# MAXM86161.net
KiCad netlist of a schematic drawn in EAGLE
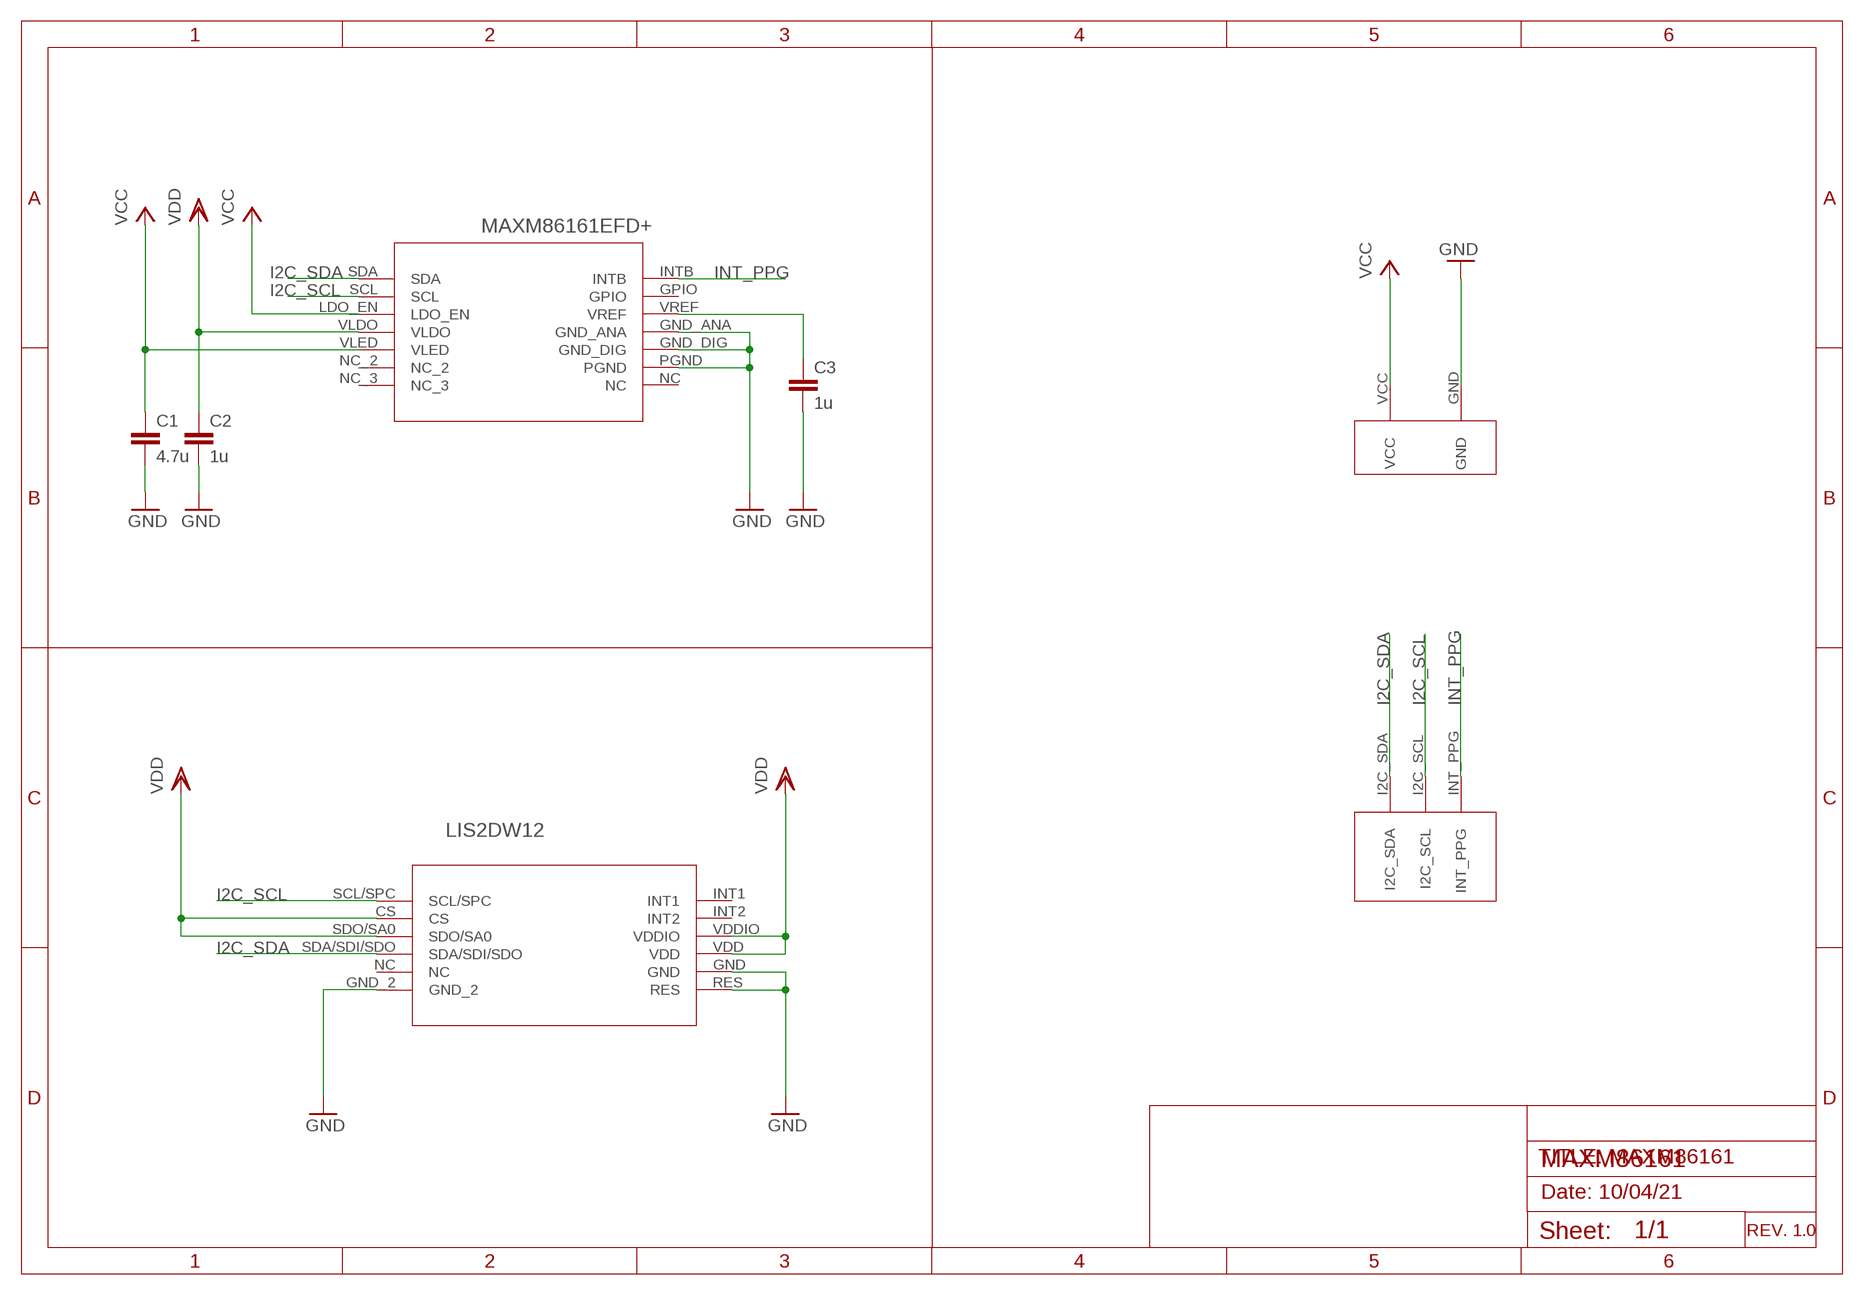
[diagram p0: schematic, sheet 1]

(export (version "E")
  (design (tool "Eeschema 10.0.6"))
  (components
    (comp (ref "C1")
      (value "4.7u")
      (footprint "eagle-import:C0603")
      (libsource (lib "eagle-import") (part "C0603"))
    )
    (comp (ref "C2")
      (value "1u")
      (footprint "eagle-import:C0402")
      (libsource (lib "eagle-import") (part "C0402"))
    )
    (comp (ref "C3")
      (value "1u")
      (footprint "eagle-import:C0402")
      (libsource (lib "eagle-import") (part "C0402"))
    )
    (comp (ref "U$1")
      (value "PAD_2")
      (footprint "eagle-import:PAD_2")
      (libsource (lib "eagle-import") (part "PAD_2"))
    )
    (comp (ref "U$2")
      (value "PAD_3")
      (footprint "eagle-import:PAD_3")
      (libsource (lib "eagle-import") (part "PAD_3"))
    )
    (comp (ref "U1")
      (value "MAXM86161EFD+")
      (footprint "eagle-import:21-100309A_MXM")
      (fields (field (name "COPYRIGHT") "Copyright (C) 2018 Accelerated Designs. All rights reserved"))
      (libsource (lib "eagle-import") (part "MAXM86161EFD+"))
    )
    (comp (ref "U2")
      (value "LIS2DW12")
      (footprint "eagle-import:LIS2DW12_LGA-12_2X2X0P7_STM")
      (libsource (lib "eagle-import") (part "LIS2DW12"))
    )
  )
  (nets
    (net (code "1") (name "/I2C_SCL") (class "Default")
      (node (ref "U$2") (pin "I2C_SCL") (pinfunction "I2C_SCL_I2C_SCL") (pintype "bidirectional"))
      (node (ref "U1") (pin "SCL") (pinfunction "SCL_SCL") (pintype "input"))
      (node (ref "U2") (pin "SCL/SPC") (pinfunction "SCL/SPC_SCL/SPC") (pintype "bidirectional"))
    )
    (net (code "2") (name "/I2C_SDA") (class "Default")
      (node (ref "U$2") (pin "I2C_SDA") (pinfunction "I2C_SDA_I2C_SDA") (pintype "bidirectional"))
      (node (ref "U1") (pin "SDA") (pinfunction "SDA_SDA") (pintype "bidirectional"))
      (node (ref "U2") (pin "SDA/SDI/SDO") (pinfunction "SDA/SDI/SDO_SDA/SDI/SDO") (pintype "bidirectional"))
    )
    (net (code "3") (name "/INT_PPG") (class "Default")
      (node (ref "U$2") (pin "INT_PPG") (pinfunction "INT_PPG_INT_PPG") (pintype "bidirectional"))
      (node (ref "U1") (pin "INTB") (pinfunction "INTB_INTB") (pintype "passive"))
    )
    (net (code "4") (name "GND") (class "Default")
      (node (ref "C1") (pin "P$2") (pinfunction "2_P$2") (pintype "passive"))
      (node (ref "C2") (pin "P$2") (pinfunction "2_P$2") (pintype "passive"))
      (node (ref "C3") (pin "P$2") (pinfunction "2_P$2") (pintype "passive"))
      (node (ref "U$1") (pin "GND") (pinfunction "GND_GND") (pintype "bidirectional"))
      (node (ref "U1") (pin "GND_ANA") (pinfunction "GND_ANA_GND_ANA") (pintype "passive"))
      (node (ref "U1") (pin "GND_DIG") (pinfunction "GND_DIG_GND_DIG") (pintype "passive"))
      (node (ref "U1") (pin "PGND") (pinfunction "PGND_PGND") (pintype "passive"))
      (node (ref "U2") (pin "GND") (pinfunction "GND_GND") (pintype "passive"))
      (node (ref "U2") (pin "GND_2") (pinfunction "GND_2_GND_2") (pintype "passive"))
      (node (ref "U2") (pin "RES") (pinfunction "RES_RES") (pintype "passive"))
    )
    (net (code "5") (name "Net-(C3-1)") (class "Default")
      (node (ref "C3") (pin "P$1") (pinfunction "1_P$1") (pintype "passive"))
      (node (ref "U1") (pin "VREF") (pinfunction "VREF_VREF") (pintype "passive"))
    )
    (net (code "6") (name "VCC") (class "Default")
      (node (ref "C1") (pin "P$1") (pinfunction "1_P$1") (pintype "passive"))
      (node (ref "U$1") (pin "VCC") (pinfunction "VCC_VCC") (pintype "bidirectional"))
      (node (ref "U1") (pin "LDO_EN") (pinfunction "LDO_EN_LDO_EN") (pintype "input"))
      (node (ref "U1") (pin "VLED") (pinfunction "VLED_VLED") (pintype "power_in"))
    )
    (net (code "7") (name "VDD") (class "Default")
      (node (ref "C2") (pin "P$1") (pinfunction "1_P$1") (pintype "passive"))
      (node (ref "U1") (pin "VLDO") (pinfunction "VLDO_VLDO") (pintype "power_in"))
      (node (ref "U2") (pin "CS") (pinfunction "CS_CS") (pintype "input"))
      (node (ref "U2") (pin "SDO/SA0") (pinfunction "SDO/SA0_SDO/SA0") (pintype "bidirectional"))
      (node (ref "U2") (pin "VDD") (pinfunction "VDD_VDD") (pintype "power_in"))
      (node (ref "U2") (pin "VDDIO") (pinfunction "VDDIO_VDDIO") (pintype "power_in"))
    )
    (net (code "8") (name "unconnected-(U1-PadGPIO)") (class "Default")
      (node (ref "U1") (pin "GPIO") (pinfunction "GPIO_GPIO") (pintype "bidirectional"))
    )
    (net (code "9") (name "unconnected-(U1-PadNC)") (class "Default")
      (node (ref "U1") (pin "NC") (pinfunction "NC_NC") (pintype "no_connect"))
    )
    (net (code "10") (name "unconnected-(U1-PadNC_2)") (class "Default")
      (node (ref "U1") (pin "NC_2") (pinfunction "NC_2_NC_2") (pintype "no_connect"))
    )
    (net (code "11") (name "unconnected-(U1-PadNC_3)") (class "Default")
      (node (ref "U1") (pin "NC_3") (pinfunction "NC_3_NC_3") (pintype "no_connect"))
    )
    (net (code "12") (name "unconnected-(U2-PadINT1)") (class "Default")
      (node (ref "U2") (pin "INT1") (pinfunction "INT1_INT1") (pintype "output"))
    )
    (net (code "13") (name "unconnected-(U2-PadINT2)") (class "Default")
      (node (ref "U2") (pin "INT2") (pinfunction "INT2_INT2") (pintype "output"))
    )
    (net (code "14") (name "unconnected-(U2-PadNC)") (class "Default")
      (node (ref "U2") (pin "NC") (pinfunction "NC_NC") (pintype "no_connect"))
    )
  )
)
